# Transmitter.net
KiCad netlist of a schematic drawn in Altium Designer
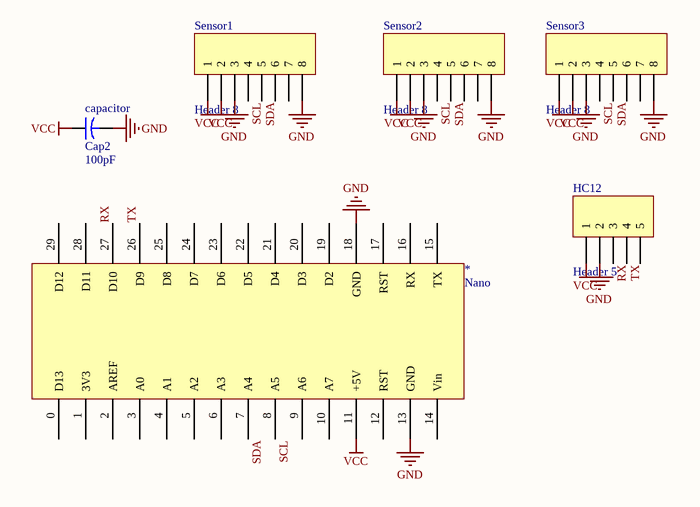
[diagram p0: Transmitter.SchDoc]

(export (version "E")
  (design (tool "Eeschema 10.0.6"))
  (components
    (comp (ref "*")
      (value "Nano")
      (footprint "ArduinoNano:ArduinoNano")
      (libsource (lib "ArduinoNano") (part "Component_1"))
    )
    (comp (ref "capacitor")
      (value "Cap2")
      (footprint "CAPR5-4X5")
      (description "Capacitor")
      (fields (field (name "ALTIUM_VALUE") "100pF") (field (name "PUBLISHER") "Altium Limited"))
      (libsource (lib "Miscellaneous Devices") (part "Cap2"))
    )
    (comp (ref "HC12")
      (value "Header 5")
      (footprint "HDR1X5")
      (description "Header, 5-Pin")
      (fields (field (name "PUBLISHER") "Altium Limited"))
      (libsource (lib "Miscellaneous Connectors") (part "Header 5"))
    )
    (comp (ref "Sensor1")
      (value "Header 8")
      (footprint "HDR1X8")
      (description "Header, 8-Pin")
      (fields (field (name "PUBLISHER") "Altium Limited"))
      (libsource (lib "Miscellaneous Connectors") (part "Header 8"))
    )
    (comp (ref "Sensor2")
      (value "Header 8")
      (footprint "HDR1X8")
      (description "Header, 8-Pin")
      (fields (field (name "PUBLISHER") "Altium Limited"))
      (libsource (lib "Miscellaneous Connectors") (part "Header 8"))
    )
    (comp (ref "Sensor3")
      (value "Header 8")
      (footprint "HDR1X8")
      (description "Header, 8-Pin")
      (fields (field (name "PUBLISHER") "Altium Limited"))
      (libsource (lib "Miscellaneous Connectors") (part "Header 8"))
    )
  )
  (nets
    (net (code "1") (name "/RX") (class "Default")
      (node (ref "*") (pin "27") (pinfunction "D10_27") (pintype "passive"))
      (node (ref "HC12") (pin "3") (pinfunction "3_3") (pintype "passive"))
    )
    (net (code "2") (name "/SCL") (class "Default")
      (node (ref "*") (pin "8") (pinfunction "A5_8") (pintype "passive"))
      (node (ref "Sensor1") (pin "4") (pinfunction "4_4") (pintype "passive"))
      (node (ref "Sensor2") (pin "4") (pinfunction "4_4") (pintype "passive"))
      (node (ref "Sensor3") (pin "4") (pinfunction "4_4") (pintype "passive"))
    )
    (net (code "3") (name "/SDA") (class "Default")
      (node (ref "*") (pin "7") (pinfunction "A4_7") (pintype "passive"))
      (node (ref "Sensor1") (pin "5") (pinfunction "5_5") (pintype "passive"))
      (node (ref "Sensor2") (pin "5") (pinfunction "5_5") (pintype "passive"))
      (node (ref "Sensor3") (pin "5") (pinfunction "5_5") (pintype "passive"))
    )
    (net (code "4") (name "/TX") (class "Default")
      (node (ref "*") (pin "26") (pinfunction "D9_26") (pintype "passive"))
      (node (ref "HC12") (pin "4") (pinfunction "4_4") (pintype "passive"))
    )
    (net (code "5") (name "GND") (class "Default")
      (node (ref "*") (pin "13") (pinfunction "GND_13") (pintype "passive"))
      (node (ref "*") (pin "18") (pinfunction "GND_18") (pintype "passive"))
      (node (ref "HC12") (pin "2") (pinfunction "2_2") (pintype "passive"))
      (node (ref "Sensor1") (pin "3") (pinfunction "3_3") (pintype "passive"))
      (node (ref "Sensor1") (pin "8") (pinfunction "8_8") (pintype "passive"))
      (node (ref "Sensor2") (pin "3") (pinfunction "3_3") (pintype "passive"))
      (node (ref "Sensor2") (pin "8") (pinfunction "8_8") (pintype "passive"))
      (node (ref "Sensor3") (pin "3") (pinfunction "3_3") (pintype "passive"))
      (node (ref "Sensor3") (pin "8") (pinfunction "8_8") (pintype "passive"))
      (node (ref "capacitor") (pin "2") (pinfunction "2_2") (pintype "passive"))
    )
    (net (code "6") (name "VCC") (class "Default")
      (node (ref "*") (pin "11") (pinfunction "+5V_11") (pintype "passive"))
      (node (ref "HC12") (pin "1") (pinfunction "1_1") (pintype "passive"))
      (node (ref "Sensor1") (pin "1") (pinfunction "1_1") (pintype "passive"))
      (node (ref "Sensor1") (pin "2") (pinfunction "2_2") (pintype "passive"))
      (node (ref "Sensor2") (pin "1") (pinfunction "1_1") (pintype "passive"))
      (node (ref "Sensor2") (pin "2") (pinfunction "2_2") (pintype "passive"))
      (node (ref "Sensor3") (pin "1") (pinfunction "1_1") (pintype "passive"))
      (node (ref "Sensor3") (pin "2") (pinfunction "2_2") (pintype "passive"))
      (node (ref "capacitor") (pin "1") (pinfunction "1_1") (pintype "passive"))
    )
    (net (code "7") (name "unconnected-(*-3V3-Pad1)") (class "Default")
      (node (ref "*") (pin "1") (pinfunction "3V3_1") (pintype "passive"))
    )
    (net (code "8") (name "unconnected-(*-A0-Pad3)") (class "Default")
      (node (ref "*") (pin "3") (pinfunction "A0_3") (pintype "passive"))
    )
    (net (code "9") (name "unconnected-(*-A1-Pad4)") (class "Default")
      (node (ref "*") (pin "4") (pinfunction "A1_4") (pintype "passive"))
    )
    (net (code "10") (name "unconnected-(*-A2-Pad5)") (class "Default")
      (node (ref "*") (pin "5") (pinfunction "A2_5") (pintype "passive"))
    )
    (net (code "11") (name "unconnected-(*-A3-Pad6)") (class "Default")
      (node (ref "*") (pin "6") (pinfunction "A3_6") (pintype "passive"))
    )
    (net (code "12") (name "unconnected-(*-A6-Pad9)") (class "Default")
      (node (ref "*") (pin "9") (pinfunction "A6_9") (pintype "passive"))
    )
    (net (code "13") (name "unconnected-(*-A7-Pad10)") (class "Default")
      (node (ref "*") (pin "10") (pinfunction "A7_10") (pintype "passive"))
    )
    (net (code "14") (name "unconnected-(*-AREF-Pad2)") (class "Default")
      (node (ref "*") (pin "2") (pinfunction "AREF_2") (pintype "passive"))
    )
    (net (code "15") (name "unconnected-(*-D2-Pad19)") (class "Default")
      (node (ref "*") (pin "19") (pinfunction "D2_19") (pintype "passive"))
    )
    (net (code "16") (name "unconnected-(*-D3-Pad20)") (class "Default")
      (node (ref "*") (pin "20") (pinfunction "D3_20") (pintype "passive"))
    )
    (net (code "17") (name "unconnected-(*-D4-Pad21)") (class "Default")
      (node (ref "*") (pin "21") (pinfunction "D4_21") (pintype "passive"))
    )
    (net (code "18") (name "unconnected-(*-D5-Pad22)") (class "Default")
      (node (ref "*") (pin "22") (pinfunction "D5_22") (pintype "passive"))
    )
    (net (code "19") (name "unconnected-(*-D6-Pad23)") (class "Default")
      (node (ref "*") (pin "23") (pinfunction "D6_23") (pintype "passive"))
    )
    (net (code "20") (name "unconnected-(*-D7-Pad24)") (class "Default")
      (node (ref "*") (pin "24") (pinfunction "D7_24") (pintype "passive"))
    )
    (net (code "21") (name "unconnected-(*-D8-Pad25)") (class "Default")
      (node (ref "*") (pin "25") (pinfunction "D8_25") (pintype "passive"))
    )
    (net (code "22") (name "unconnected-(*-D11-Pad28)") (class "Default")
      (node (ref "*") (pin "28") (pinfunction "D11_28") (pintype "passive"))
    )
    (net (code "23") (name "unconnected-(*-D12-Pad29)") (class "Default")
      (node (ref "*") (pin "29") (pinfunction "D12_29") (pintype "passive"))
    )
    (net (code "24") (name "unconnected-(*-D13-Pad0)") (class "Default")
      (node (ref "*") (pin "0") (pinfunction "D13_0") (pintype "passive"))
    )
    (net (code "25") (name "unconnected-(*-RST-Pad12)") (class "Default")
      (node (ref "*") (pin "12") (pinfunction "RST_12") (pintype "passive"))
    )
    (net (code "26") (name "unconnected-(*-RST-Pad17)") (class "Default")
      (node (ref "*") (pin "17") (pinfunction "RST_17") (pintype "passive"))
    )
    (net (code "27") (name "unconnected-(*-RX-Pad16)") (class "Default")
      (node (ref "*") (pin "16") (pinfunction "RX_16") (pintype "passive"))
    )
    (net (code "28") (name "unconnected-(*-TX-Pad15)") (class "Default")
      (node (ref "*") (pin "15") (pinfunction "TX_15") (pintype "passive"))
    )
    (net (code "29") (name "unconnected-(*-Vin-Pad14)") (class "Default")
      (node (ref "*") (pin "14") (pinfunction "Vin_14") (pintype "passive"))
    )
    (net (code "30") (name "unconnected-(HC12-Pad5)") (class "Default")
      (node (ref "HC12") (pin "5") (pinfunction "5_5") (pintype "passive"))
    )
    (net (code "31") (name "unconnected-(Sensor1-Pad6)") (class "Default")
      (node (ref "Sensor1") (pin "6") (pinfunction "6_6") (pintype "passive"))
    )
    (net (code "32") (name "unconnected-(Sensor1-Pad7)") (class "Default")
      (node (ref "Sensor1") (pin "7") (pinfunction "7_7") (pintype "passive"))
    )
    (net (code "33") (name "unconnected-(Sensor2-Pad6)") (class "Default")
      (node (ref "Sensor2") (pin "6") (pinfunction "6_6") (pintype "passive"))
    )
    (net (code "34") (name "unconnected-(Sensor2-Pad7)") (class "Default")
      (node (ref "Sensor2") (pin "7") (pinfunction "7_7") (pintype "passive"))
    )
    (net (code "35") (name "unconnected-(Sensor3-Pad6)") (class "Default")
      (node (ref "Sensor3") (pin "6") (pinfunction "6_6") (pintype "passive"))
    )
    (net (code "36") (name "unconnected-(Sensor3-Pad7)") (class "Default")
      (node (ref "Sensor3") (pin "7") (pinfunction "7_7") (pintype "passive"))
    )
  )
)
